# MUR_V0_1_Wiring.net
KiCad netlist of a schematic drawn in EAGLE
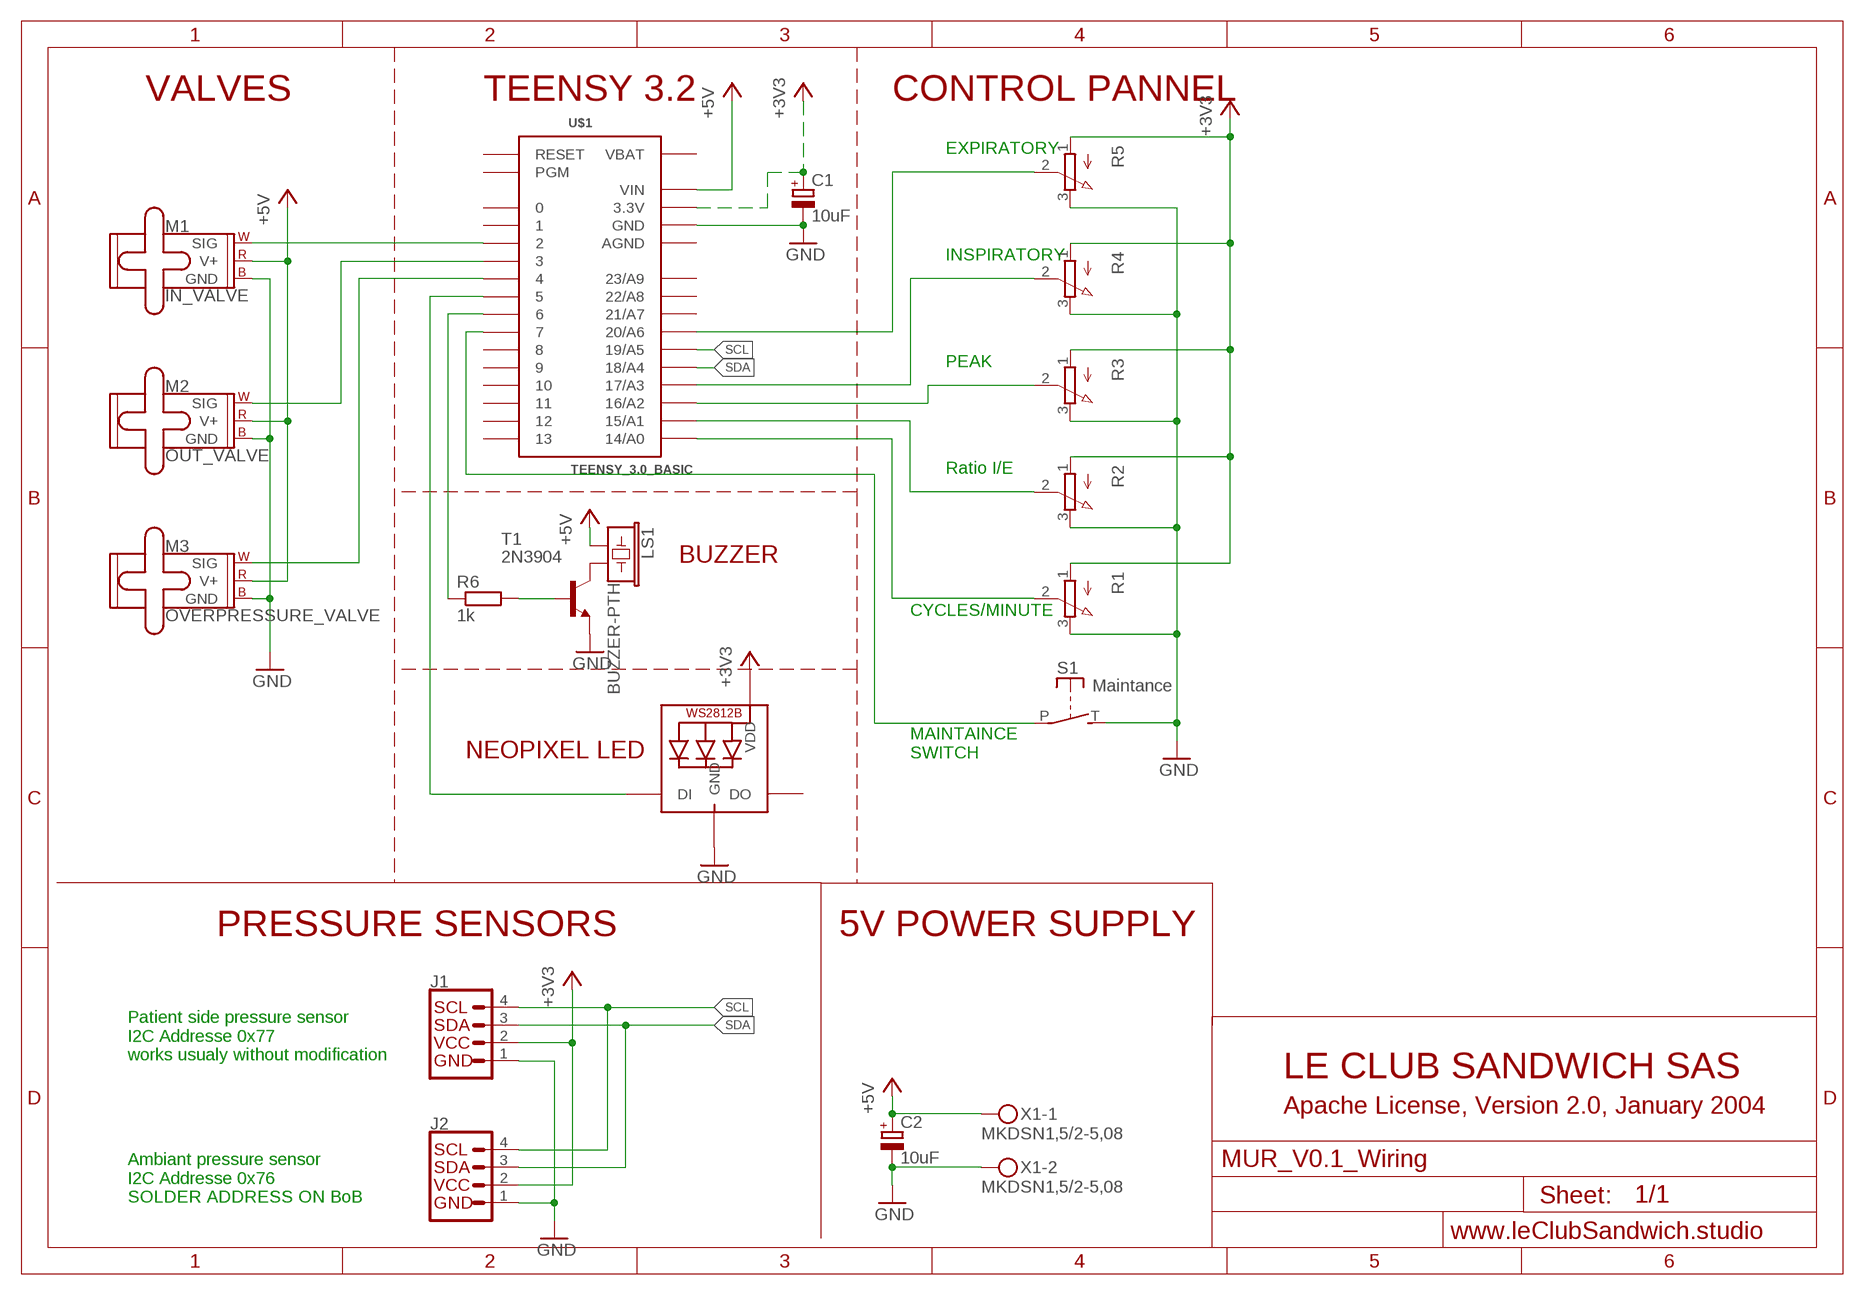
[diagram p0: schematic, sheet 1]

(export (version "E")
  (design (tool "Eeschema 10.0.6"))
  (components
    (comp (ref "C1")
      (value "10uF")
      (footprint "eagle-import:E2,5-6")
      (libsource (lib "eagle-import") (part "CPOL-EUE2.5-6"))
    )
    (comp (ref "C2")
      (value "10uF")
      (footprint "eagle-import:E2,5-6")
      (libsource (lib "eagle-import") (part "CPOL-EUE2.5-6"))
    )
    (comp (ref "J1")
      (value "I2C_STANDARD_NO_SILK")
      (footprint "eagle-import:1X04_NO_SILK")
      (libsource (lib "eagle-import") (part "I2C_STANDARD_NO_SILK"))
    )
    (comp (ref "J2")
      (value "I2C_STANDARD_NO_SILK")
      (footprint "eagle-import:1X04_NO_SILK")
      (libsource (lib "eagle-import") (part "I2C_STANDARD_NO_SILK"))
    )
    (comp (ref "LED1")
      (value "WS2812B5050")
      (footprint "eagle-import:WS2812B")
      (libsource (lib "eagle-import") (part "WS2812B5050"))
    )
    (comp (ref "LS1")
      (value "BUZZER-PTH")
      (footprint "eagle-import:BUZZER-12MM")
      (libsource (lib "eagle-import") (part "BUZZER-PTH"))
    )
    (comp (ref "M1")
      (value "IN_VALVE")
      (footprint "eagle-import:1X03")
      (libsource (lib "eagle-import") (part "SERVO"))
    )
    (comp (ref "M2")
      (value "OUT_VALVE")
      (footprint "eagle-import:1X03")
      (libsource (lib "eagle-import") (part "SERVO"))
    )
    (comp (ref "M3")
      (value "OVERPRESSURE_VALVE")
      (footprint "eagle-import:1X03")
      (libsource (lib "eagle-import") (part "SERVO"))
    )
    (comp (ref "R1")
      (value "3RP/1610N")
      (footprint "eagle-import:3RP_1610N")
      (libsource (lib "eagle-import") (part "3RP/1610N"))
    )
    (comp (ref "R2")
      (value "3RP/1610N")
      (footprint "eagle-import:3RP_1610N")
      (libsource (lib "eagle-import") (part "3RP/1610N"))
    )
    (comp (ref "R3")
      (value "3RP/1610N")
      (footprint "eagle-import:3RP_1610N")
      (libsource (lib "eagle-import") (part "3RP/1610N"))
    )
    (comp (ref "R4")
      (value "3RP/1610N")
      (footprint "eagle-import:3RP_1610N")
      (libsource (lib "eagle-import") (part "3RP/1610N"))
    )
    (comp (ref "R5")
      (value "3RP/1610N")
      (footprint "eagle-import:3RP_1610N")
      (libsource (lib "eagle-import") (part "3RP/1610N"))
    )
    (comp (ref "R6")
      (value "1k")
      (footprint "eagle-import:0204_5")
      (libsource (lib "eagle-import") (part "R-EU_0204/5"))
    )
    (comp (ref "S1")
      (value "Maintance")
      (footprint "eagle-import:JUDCOSPST")
      (libsource (lib "eagle-import") (part "SPST"))
    )
    (comp (ref "T1")
      (value "2N3904")
      (footprint "eagle-import:TO92")
      (libsource (lib "eagle-import") (part "2N3904"))
    )
    (comp (ref "U$1")
      (value "TEENSY_3.0_BASIC")
      (footprint "eagle-import:TEENSY_3.0_BASIC")
      (libsource (lib "eagle-import") (part "TEENSY_3.0_BASIC"))
    )
    (comp (ref "X1")
      (value "MKDSN1,5/2-5,08")
      (footprint "eagle-import:MKDSN1,5_2-5,08")
      (libsource (lib "eagle-import") (part "MKDSN1,5/2-5,08"))
    )
  )
  (nets
    (net (code "1") (name "+3V3") (class "Default")
      (node (ref "C1") (pin "+") (pinfunction "+_+") (pintype "passive"))
      (node (ref "J1") (pin "2") (pinfunction "2_2") (pintype "power_in"))
      (node (ref "J2") (pin "2") (pinfunction "2_2") (pintype "power_in"))
      (node (ref "LED1") (pin "1-VDD") (pinfunction "VDD_1-VDD") (pintype "power_in"))
      (node (ref "R1") (pin "1") (pinfunction "A_1") (pintype "passive"))
      (node (ref "R2") (pin "1") (pinfunction "A_1") (pintype "passive"))
      (node (ref "R3") (pin "1") (pinfunction "A_1") (pintype "passive"))
      (node (ref "R4") (pin "1") (pinfunction "A_1") (pintype "passive"))
      (node (ref "R5") (pin "1") (pinfunction "A_1") (pintype "passive"))
      (node (ref "U$1") (pin "3.3V") (pinfunction "3.3V_3.3V") (pintype "power_in"))
      (node (ref "U$1") (pin "3.3V1") (pinfunction "3.3V_3.3V1") (pintype "power_in"))
    )
    (net (code "2") (name "+5V") (class "Default")
      (node (ref "C2") (pin "+") (pinfunction "+_+") (pintype "passive"))
      (node (ref "LS1") (pin "+") (pinfunction "1_+") (pintype "passive"))
      (node (ref "M1") (pin "2") (pinfunction "V+_2") (pintype "bidirectional"))
      (node (ref "M2") (pin "2") (pinfunction "V+_2") (pintype "bidirectional"))
      (node (ref "M3") (pin "2") (pinfunction "V+_2") (pintype "bidirectional"))
      (node (ref "U$1") (pin "VIN") (pinfunction "VIN_VIN") (pintype "power_in"))
      (node (ref "X1") (pin "1") (pinfunction "KL_1") (pintype "passive"))
    )
    (net (code "3") (name "/AGND") (class "Default")
      (node (ref "U$1") (pin "AGND") (pinfunction "AGND_AGND") (pintype "power_in"))
    )
    (net (code "4") (name "/VBAT") (class "Default")
      (node (ref "U$1") (pin "VBAT") (pinfunction "VBAT_VBAT") (pintype "power_in"))
    )
    (net (code "5") (name "GND") (class "Default")
      (node (ref "C1") (pin "-") (pinfunction "-_-") (pintype "passive"))
      (node (ref "C2") (pin "-") (pinfunction "-_-") (pintype "passive"))
      (node (ref "J1") (pin "1") (pinfunction "1_1") (pintype "power_in"))
      (node (ref "J2") (pin "1") (pinfunction "1_1") (pintype "power_in"))
      (node (ref "LED1") (pin "3-GND") (pinfunction "GND_3-GND") (pintype "power_in"))
      (node (ref "M1") (pin "3") (pinfunction "GND_3") (pintype "bidirectional"))
      (node (ref "M2") (pin "3") (pinfunction "GND_3") (pintype "bidirectional"))
      (node (ref "M3") (pin "3") (pinfunction "GND_3") (pintype "bidirectional"))
      (node (ref "R1") (pin "3") (pinfunction "E_3") (pintype "passive"))
      (node (ref "R2") (pin "3") (pinfunction "E_3") (pintype "passive"))
      (node (ref "R3") (pin "3") (pinfunction "E_3") (pintype "passive"))
      (node (ref "R4") (pin "3") (pinfunction "E_3") (pintype "passive"))
      (node (ref "R5") (pin "3") (pinfunction "E_3") (pintype "passive"))
      (node (ref "S1") (pin "T") (pinfunction "S_T") (pintype "passive"))
      (node (ref "T1") (pin "3") (pinfunction "E_3") (pintype "passive"))
      (node (ref "U$1") (pin "GND") (pinfunction "GND_GND") (pintype "power_in"))
      (node (ref "U$1") (pin "GND1") (pinfunction "GND_GND1") (pintype "power_in"))
      (node (ref "X1") (pin "2") (pinfunction "KL_2") (pintype "passive"))
    )
    (net (code "6") (name "Net-(LED1-DI)") (class "Default")
      (node (ref "LED1") (pin "4-DIN") (pinfunction "DI_4-DIN") (pintype "input"))
      (node (ref "U$1") (pin "5") (pinfunction "5_5") (pintype "bidirectional"))
    )
    (net (code "7") (name "Net-(LS1-2)") (class "Default")
      (node (ref "LS1") (pin "-") (pinfunction "2_-") (pintype "passive"))
      (node (ref "T1") (pin "1") (pinfunction "C_1") (pintype "passive"))
    )
    (net (code "8") (name "Net-(M1-SIG)") (class "Default")
      (node (ref "M1") (pin "1") (pinfunction "SIG_1") (pintype "bidirectional"))
      (node (ref "U$1") (pin "2") (pinfunction "2_2") (pintype "bidirectional"))
    )
    (net (code "9") (name "Net-(M2-SIG)") (class "Default")
      (node (ref "M2") (pin "1") (pinfunction "SIG_1") (pintype "bidirectional"))
      (node (ref "U$1") (pin "3") (pinfunction "3_3") (pintype "bidirectional"))
    )
    (net (code "10") (name "Net-(M3-SIG)") (class "Default")
      (node (ref "M3") (pin "1") (pinfunction "SIG_1") (pintype "bidirectional"))
      (node (ref "U$1") (pin "4") (pinfunction "4_4") (pintype "bidirectional"))
    )
    (net (code "11") (name "Net-(R1-S)") (class "Default")
      (node (ref "R1") (pin "2") (pinfunction "S_2") (pintype "passive"))
      (node (ref "U$1") (pin "14/A0") (pinfunction "14/A0_14/A0") (pintype "bidirectional"))
    )
    (net (code "12") (name "Net-(R2-S)") (class "Default")
      (node (ref "R2") (pin "2") (pinfunction "S_2") (pintype "passive"))
      (node (ref "U$1") (pin "15/A1") (pinfunction "15/A1_15/A1") (pintype "bidirectional"))
    )
    (net (code "13") (name "Net-(R3-S)") (class "Default")
      (node (ref "R3") (pin "2") (pinfunction "S_2") (pintype "passive"))
      (node (ref "U$1") (pin "16/A2") (pinfunction "16/A2_16/A2") (pintype "bidirectional"))
    )
    (net (code "14") (name "Net-(R4-S)") (class "Default")
      (node (ref "R4") (pin "2") (pinfunction "S_2") (pintype "passive"))
      (node (ref "U$1") (pin "17/A3") (pinfunction "17/A3_17/A3") (pintype "bidirectional"))
    )
    (net (code "15") (name "Net-(R5-S)") (class "Default")
      (node (ref "R5") (pin "2") (pinfunction "S_2") (pintype "passive"))
      (node (ref "U$1") (pin "20/A6") (pinfunction "20/A6_20/A6") (pintype "bidirectional"))
    )
    (net (code "16") (name "Net-(R6-Pad1)") (class "Default")
      (node (ref "R6") (pin "1") (pinfunction "1_1") (pintype "passive"))
      (node (ref "U$1") (pin "6") (pinfunction "6_6") (pintype "bidirectional"))
    )
    (net (code "17") (name "Net-(S1-PadP)") (class "Default")
      (node (ref "S1") (pin "P") (pinfunction "P_P") (pintype "passive"))
      (node (ref "U$1") (pin "7") (pinfunction "7_7") (pintype "bidirectional"))
    )
    (net (code "18") (name "Net-(T1-B)") (class "Default")
      (node (ref "R6") (pin "2") (pinfunction "2_2") (pintype "passive"))
      (node (ref "T1") (pin "2") (pinfunction "B_2") (pintype "passive"))
    )
    (net (code "19") (name "SCL") (class "Default")
      (node (ref "J1") (pin "4") (pinfunction "4_4") (pintype "passive"))
      (node (ref "J2") (pin "4") (pinfunction "4_4") (pintype "passive"))
      (node (ref "U$1") (pin "19/A5") (pinfunction "19/A5_19/A5") (pintype "bidirectional"))
    )
    (net (code "20") (name "SDA") (class "Default")
      (node (ref "J1") (pin "3") (pinfunction "3_3") (pintype "passive"))
      (node (ref "J2") (pin "3") (pinfunction "3_3") (pintype "passive"))
      (node (ref "U$1") (pin "18/A4") (pinfunction "18/A4_18/A4") (pintype "bidirectional"))
    )
    (net (code "21") (name "unconnected-(LED1-DO-Pad2-DOUT)") (class "Default")
      (node (ref "LED1") (pin "2-DOUT") (pinfunction "DO_2-DOUT") (pintype "output"))
    )
    (net (code "22") (name "unconnected-(U$1-Pad0)") (class "Default")
      (node (ref "U$1") (pin "0") (pinfunction "0_0") (pintype "bidirectional"))
    )
    (net (code "23") (name "unconnected-(U$1-Pad1)") (class "Default")
      (node (ref "U$1") (pin "1") (pinfunction "1_1") (pintype "bidirectional"))
    )
    (net (code "24") (name "unconnected-(U$1-Pad8)") (class "Default")
      (node (ref "U$1") (pin "8") (pinfunction "8_8") (pintype "bidirectional"))
    )
    (net (code "25") (name "unconnected-(U$1-Pad9)") (class "Default")
      (node (ref "U$1") (pin "9") (pinfunction "9_9") (pintype "bidirectional"))
    )
    (net (code "26") (name "unconnected-(U$1-Pad10)") (class "Default")
      (node (ref "U$1") (pin "10") (pinfunction "10_10") (pintype "bidirectional"))
    )
    (net (code "27") (name "unconnected-(U$1-Pad11)") (class "Default")
      (node (ref "U$1") (pin "11") (pinfunction "11_11") (pintype "bidirectional"))
    )
    (net (code "28") (name "unconnected-(U$1-Pad12)") (class "Default")
      (node (ref "U$1") (pin "12") (pinfunction "12_12") (pintype "bidirectional"))
    )
    (net (code "29") (name "unconnected-(U$1-Pad13)") (class "Default")
      (node (ref "U$1") (pin "13") (pinfunction "13_13") (pintype "bidirectional"))
    )
    (net (code "30") (name "unconnected-(U$1-Pad21{slash}A7)") (class "Default")
      (node (ref "U$1") (pin "21/A7") (pinfunction "21/A7_21/A7") (pintype "bidirectional"))
    )
    (net (code "31") (name "unconnected-(U$1-Pad22{slash}A8)") (class "Default")
      (node (ref "U$1") (pin "22/A8") (pinfunction "22/A8_22/A8") (pintype "bidirectional"))
    )
    (net (code "32") (name "unconnected-(U$1-Pad23{slash}A9)") (class "Default")
      (node (ref "U$1") (pin "23/A9") (pinfunction "23/A9_23/A9") (pintype "bidirectional"))
    )
    (net (code "33") (name "unconnected-(U$1-PadPGM)") (class "Default")
      (node (ref "U$1") (pin "PGM") (pinfunction "PGM_PGM") (pintype "bidirectional"))
    )
    (net (code "34") (name "unconnected-(U$1-PadRESET)") (class "Default")
      (node (ref "U$1") (pin "RESET") (pinfunction "RESET_RESET") (pintype "bidirectional"))
    )
  )
)
